# USBasp.net
KiCad netlist of a schematic drawn in EAGLE
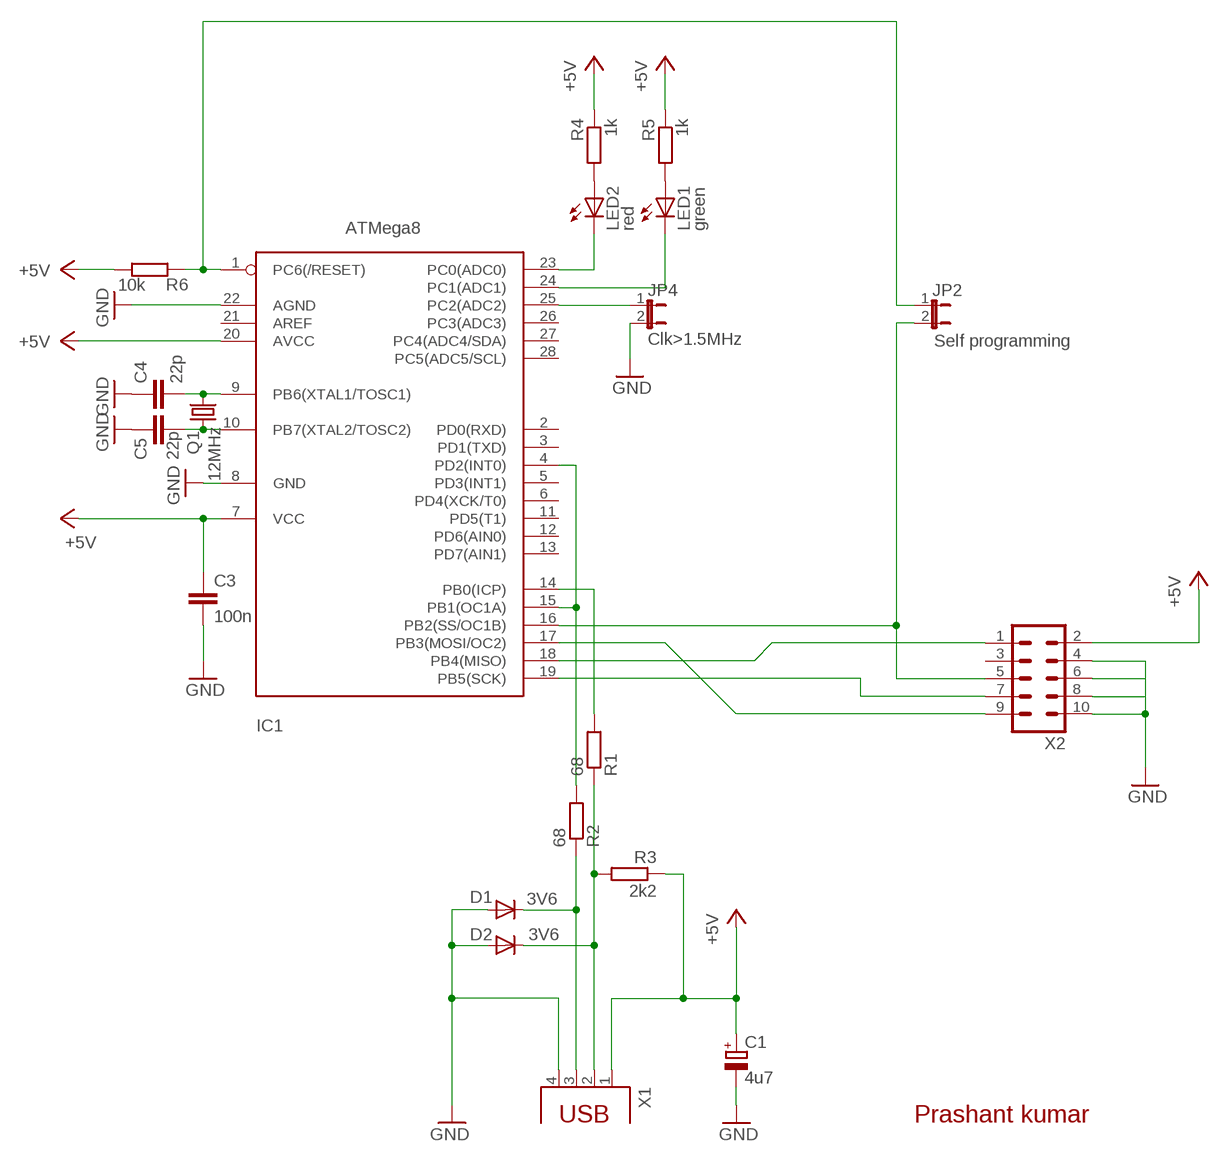
[diagram p0: schematic, sheet 1]

(export (version "E")
  (design (tool "Eeschema 10.0.6"))
  (components
    (comp (ref "C1")
      (value "4u7")
      (footprint "eagle-import:E2,5-5")
      (libsource (lib "eagle-import") (part "CPOL-EUE2.5-5"))
    )
    (comp (ref "C3")
      (value "100n")
      (footprint "eagle-import:C1206K")
      (libsource (lib "eagle-import") (part "C-EUC1206K"))
    )
    (comp (ref "C4")
      (value "22p")
      (footprint "eagle-import:C1206K")
      (libsource (lib "eagle-import") (part "C-EUC1206K"))
    )
    (comp (ref "C5")
      (value "22p")
      (footprint "eagle-import:C1206K")
      (libsource (lib "eagle-import") (part "C-EUC1206K"))
    )
    (comp (ref "D1")
      (value "3V6")
      (footprint "eagle-import:SOD80C")
      (libsource (lib "eagle-import") (part "PMLL41SOD80C"))
    )
    (comp (ref "D2")
      (value "3V6")
      (footprint "eagle-import:SOD80C")
      (libsource (lib "eagle-import") (part "PMLL41SOD80C"))
    )
    (comp (ref "IC1")
      (value "ATMega8")
      (footprint "eagle-import:DIL28-3")
      (libsource (lib "eagle-import") (part "MEGA8-P"))
    )
    (comp (ref "JP2")
      (value "Self programming")
      (footprint "eagle-import:JP1")
      (libsource (lib "eagle-import") (part "JP1E"))
    )
    (comp (ref "JP4")
      (value "Clk>1.5MHz")
      (footprint "eagle-import:JP1")
      (libsource (lib "eagle-import") (part "JP1E"))
    )
    (comp (ref "LED1")
      (value "green")
      (footprint "eagle-import:LED3MM")
      (libsource (lib "eagle-import") (part "LED3MM"))
    )
    (comp (ref "LED2")
      (value "red")
      (footprint "eagle-import:LED3MM")
      (libsource (lib "eagle-import") (part "LED3MM"))
    )
    (comp (ref "Q1")
      (value "12MHz")
      (footprint "eagle-import:HC49_S")
      (libsource (lib "eagle-import") (part "CRYTALHC49S"))
    )
    (comp (ref "R1")
      (value "68")
      (footprint "eagle-import:R1206W")
      (libsource (lib "eagle-import") (part "R-EU_R1206W"))
    )
    (comp (ref "R2")
      (value "68")
      (footprint "eagle-import:R1206W")
      (libsource (lib "eagle-import") (part "R-EU_R1206W"))
    )
    (comp (ref "R3")
      (value "2k2")
      (footprint "eagle-import:R1206W")
      (libsource (lib "eagle-import") (part "R-EU_R1206W"))
    )
    (comp (ref "R4")
      (value "1k")
      (footprint "eagle-import:R1206W")
      (libsource (lib "eagle-import") (part "R-EU_R1206W"))
    )
    (comp (ref "R5")
      (value "1k")
      (footprint "eagle-import:R1206W")
      (libsource (lib "eagle-import") (part "R-EU_R1206W"))
    )
    (comp (ref "R6")
      (value "10k")
      (footprint "eagle-import:R1206W")
      (libsource (lib "eagle-import") (part "R-EU_R1206W"))
    )
    (comp (ref "X1")
      (value "PN61729")
      (footprint "eagle-import:PN61729")
      (libsource (lib "eagle-import") (part "PN61729"))
    )
    (comp (ref "X2")
      (value "ML10")
      (footprint "eagle-import:ML10")
      (libsource (lib "eagle-import") (part "ML10"))
    )
  )
  (nets
    (net (code "1") (name "+5V") (class "Default")
      (node (ref "C1") (pin "+") (pinfunction "+_+") (pintype "passive"))
      (node (ref "C3") (pin "1") (pinfunction "1_1") (pintype "passive"))
      (node (ref "IC1") (pin "20") (pinfunction "AVCC_20") (pintype "bidirectional"))
      (node (ref "IC1") (pin "7") (pinfunction "VCC_7") (pintype "bidirectional"))
      (node (ref "R3") (pin "1") (pinfunction "1_1") (pintype "passive"))
      (node (ref "R4") (pin "1") (pinfunction "1_1") (pintype "passive"))
      (node (ref "R5") (pin "1") (pinfunction "1_1") (pintype "passive"))
      (node (ref "R6") (pin "1") (pinfunction "1_1") (pintype "passive"))
      (node (ref "X1") (pin "1") (pinfunction "1_1") (pintype "bidirectional"))
      (node (ref "X2") (pin "2") (pinfunction "2_2") (pintype "passive"))
    )
    (net (code "2") (name "GND") (class "Default")
      (node (ref "C1") (pin "-") (pinfunction "-_-") (pintype "passive"))
      (node (ref "C3") (pin "2") (pinfunction "2_2") (pintype "passive"))
      (node (ref "C4") (pin "1") (pinfunction "1_1") (pintype "passive"))
      (node (ref "C5") (pin "1") (pinfunction "1_1") (pintype "passive"))
      (node (ref "D1") (pin "A") (pinfunction "A_A") (pintype "passive"))
      (node (ref "D2") (pin "A") (pinfunction "A_A") (pintype "passive"))
      (node (ref "IC1") (pin "22") (pinfunction "AGND_22") (pintype "bidirectional"))
      (node (ref "IC1") (pin "8") (pinfunction "GND_8") (pintype "bidirectional"))
      (node (ref "JP4") (pin "2") (pinfunction "2_2") (pintype "passive"))
      (node (ref "X1") (pin "4") (pinfunction "4_4") (pintype "bidirectional"))
      (node (ref "X2") (pin "10") (pinfunction "10_10") (pintype "passive"))
      (node (ref "X2") (pin "4") (pinfunction "4_4") (pintype "passive"))
      (node (ref "X2") (pin "6") (pinfunction "6_6") (pintype "passive"))
      (node (ref "X2") (pin "8") (pinfunction "8_8") (pintype "passive"))
    )
    (net (code "3") (name "Net-(D1-PadC)") (class "Default")
      (node (ref "D1") (pin "C") (pinfunction "C_C") (pintype "passive"))
      (node (ref "R2") (pin "1") (pinfunction "1_1") (pintype "passive"))
      (node (ref "X1") (pin "3") (pinfunction "3_3") (pintype "bidirectional"))
    )
    (net (code "4") (name "Net-(D2-PadC)") (class "Default")
      (node (ref "D2") (pin "C") (pinfunction "C_C") (pintype "passive"))
      (node (ref "R1") (pin "1") (pinfunction "1_1") (pintype "passive"))
      (node (ref "R3") (pin "2") (pinfunction "2_2") (pintype "passive"))
      (node (ref "X1") (pin "2") (pinfunction "2_2") (pintype "bidirectional"))
    )
    (net (code "5") (name "Net-(IC1-PB0(ICP))") (class "Default")
      (node (ref "IC1") (pin "14") (pinfunction "PB0(ICP)_14") (pintype "bidirectional"))
      (node (ref "R1") (pin "2") (pinfunction "2_2") (pintype "passive"))
    )
    (net (code "6") (name "Net-(IC1-PB1(OC1A))") (class "Default")
      (node (ref "IC1") (pin "15") (pinfunction "PB1(OC1A)_15") (pintype "bidirectional"))
      (node (ref "IC1") (pin "4") (pinfunction "PD2(INT0)_4") (pintype "bidirectional"))
      (node (ref "R2") (pin "2") (pinfunction "2_2") (pintype "passive"))
    )
    (net (code "7") (name "Net-(IC1-PB2(SS{slash}OC1B))") (class "Default")
      (node (ref "IC1") (pin "16") (pinfunction "PB2(SS/OC1B)_16") (pintype "bidirectional"))
      (node (ref "JP2") (pin "2") (pinfunction "2_2") (pintype "passive"))
      (node (ref "X2") (pin "5") (pinfunction "5_5") (pintype "passive"))
    )
    (net (code "8") (name "Net-(IC1-PB3(MOSI{slash}OC2))") (class "Default")
      (node (ref "IC1") (pin "17") (pinfunction "PB3(MOSI/OC2)_17") (pintype "bidirectional"))
      (node (ref "X2") (pin "9") (pinfunction "9_9") (pintype "passive"))
    )
    (net (code "9") (name "Net-(IC1-PB4(MISO))") (class "Default")
      (node (ref "IC1") (pin "18") (pinfunction "PB4(MISO)_18") (pintype "bidirectional"))
      (node (ref "X2") (pin "1") (pinfunction "1_1") (pintype "passive"))
    )
    (net (code "10") (name "Net-(IC1-PB5(SCK))") (class "Default")
      (node (ref "IC1") (pin "19") (pinfunction "PB5(SCK)_19") (pintype "bidirectional"))
      (node (ref "X2") (pin "7") (pinfunction "7_7") (pintype "passive"))
    )
    (net (code "11") (name "Net-(IC1-PB6(XTAL1{slash}TOSC1))") (class "Default")
      (node (ref "C4") (pin "2") (pinfunction "2_2") (pintype "passive"))
      (node (ref "IC1") (pin "9") (pinfunction "PB6(XTAL1/TOSC1)_9") (pintype "bidirectional"))
      (node (ref "Q1") (pin "2") (pinfunction "2_2") (pintype "passive"))
    )
    (net (code "12") (name "Net-(IC1-PB7(XTAL2{slash}TOSC2))") (class "Default")
      (node (ref "C5") (pin "2") (pinfunction "2_2") (pintype "passive"))
      (node (ref "IC1") (pin "10") (pinfunction "PB7(XTAL2/TOSC2)_10") (pintype "bidirectional"))
      (node (ref "Q1") (pin "1") (pinfunction "1_1") (pintype "passive"))
    )
    (net (code "13") (name "Net-(IC1-PC0(ADC0))") (class "Default")
      (node (ref "IC1") (pin "23") (pinfunction "PC0(ADC0)_23") (pintype "bidirectional"))
      (node (ref "LED2") (pin "K") (pinfunction "C_K") (pintype "passive"))
    )
    (net (code "14") (name "Net-(IC1-PC1(ADC1))") (class "Default")
      (node (ref "IC1") (pin "24") (pinfunction "PC1(ADC1)_24") (pintype "bidirectional"))
      (node (ref "LED1") (pin "K") (pinfunction "C_K") (pintype "passive"))
    )
    (net (code "15") (name "Net-(IC1-PC2(ADC2))") (class "Default")
      (node (ref "IC1") (pin "25") (pinfunction "PC2(ADC2)_25") (pintype "bidirectional"))
      (node (ref "JP4") (pin "1") (pinfunction "1_1") (pintype "passive"))
    )
    (net (code "16") (name "Net-(IC1-PC6({slash}RESET))") (class "Default")
      (node (ref "IC1") (pin "1") (pinfunction "PC6(/RESET)_1") (pintype "bidirectional"))
      (node (ref "JP2") (pin "1") (pinfunction "1_1") (pintype "passive"))
      (node (ref "R6") (pin "2") (pinfunction "2_2") (pintype "passive"))
    )
    (net (code "17") (name "Net-(LED1-PadA)") (class "Default")
      (node (ref "LED1") (pin "A") (pinfunction "A_A") (pintype "passive"))
      (node (ref "R5") (pin "2") (pinfunction "2_2") (pintype "passive"))
    )
    (net (code "18") (name "Net-(LED2-PadA)") (class "Default")
      (node (ref "LED2") (pin "A") (pinfunction "A_A") (pintype "passive"))
      (node (ref "R4") (pin "2") (pinfunction "2_2") (pintype "passive"))
    )
    (net (code "19") (name "unconnected-(IC1-AREF-Pad21)") (class "Default")
      (node (ref "IC1") (pin "21") (pinfunction "AREF_21") (pintype "bidirectional"))
    )
    (net (code "20") (name "unconnected-(IC1-PC3(ADC3)-Pad26)") (class "Default")
      (node (ref "IC1") (pin "26") (pinfunction "PC3(ADC3)_26") (pintype "bidirectional"))
    )
    (net (code "21") (name "unconnected-(IC1-PC4(ADC4{slash}SDA)-Pad27)") (class "Default")
      (node (ref "IC1") (pin "27") (pinfunction "PC4(ADC4/SDA)_27") (pintype "bidirectional"))
    )
    (net (code "22") (name "unconnected-(IC1-PC5(ADC5{slash}SCL)-Pad28)") (class "Default")
      (node (ref "IC1") (pin "28") (pinfunction "PC5(ADC5/SCL)_28") (pintype "bidirectional"))
    )
    (net (code "23") (name "unconnected-(IC1-PD0(RXD)-Pad2)") (class "Default")
      (node (ref "IC1") (pin "2") (pinfunction "PD0(RXD)_2") (pintype "bidirectional"))
    )
    (net (code "24") (name "unconnected-(IC1-PD1(TXD)-Pad3)") (class "Default")
      (node (ref "IC1") (pin "3") (pinfunction "PD1(TXD)_3") (pintype "bidirectional"))
    )
    (net (code "25") (name "unconnected-(IC1-PD3(INT1)-Pad5)") (class "Default")
      (node (ref "IC1") (pin "5") (pinfunction "PD3(INT1)_5") (pintype "bidirectional"))
    )
    (net (code "26") (name "unconnected-(IC1-PD4(XCK{slash}T0)-Pad6)") (class "Default")
      (node (ref "IC1") (pin "6") (pinfunction "PD4(XCK/T0)_6") (pintype "bidirectional"))
    )
    (net (code "27") (name "unconnected-(IC1-PD5(T1)-Pad11)") (class "Default")
      (node (ref "IC1") (pin "11") (pinfunction "PD5(T1)_11") (pintype "bidirectional"))
    )
    (net (code "28") (name "unconnected-(IC1-PD6(AIN0)-Pad12)") (class "Default")
      (node (ref "IC1") (pin "12") (pinfunction "PD6(AIN0)_12") (pintype "bidirectional"))
    )
    (net (code "29") (name "unconnected-(IC1-PD7(AIN1)-Pad13)") (class "Default")
      (node (ref "IC1") (pin "13") (pinfunction "PD7(AIN1)_13") (pintype "bidirectional"))
    )
    (net (code "30") (name "unconnected-(X2-Pad3)") (class "Default")
      (node (ref "X2") (pin "3") (pinfunction "3_3") (pintype "passive"))
    )
  )
)
